# ext_sensor_board.net
KiCad netlist of a schematic drawn in EAGLE
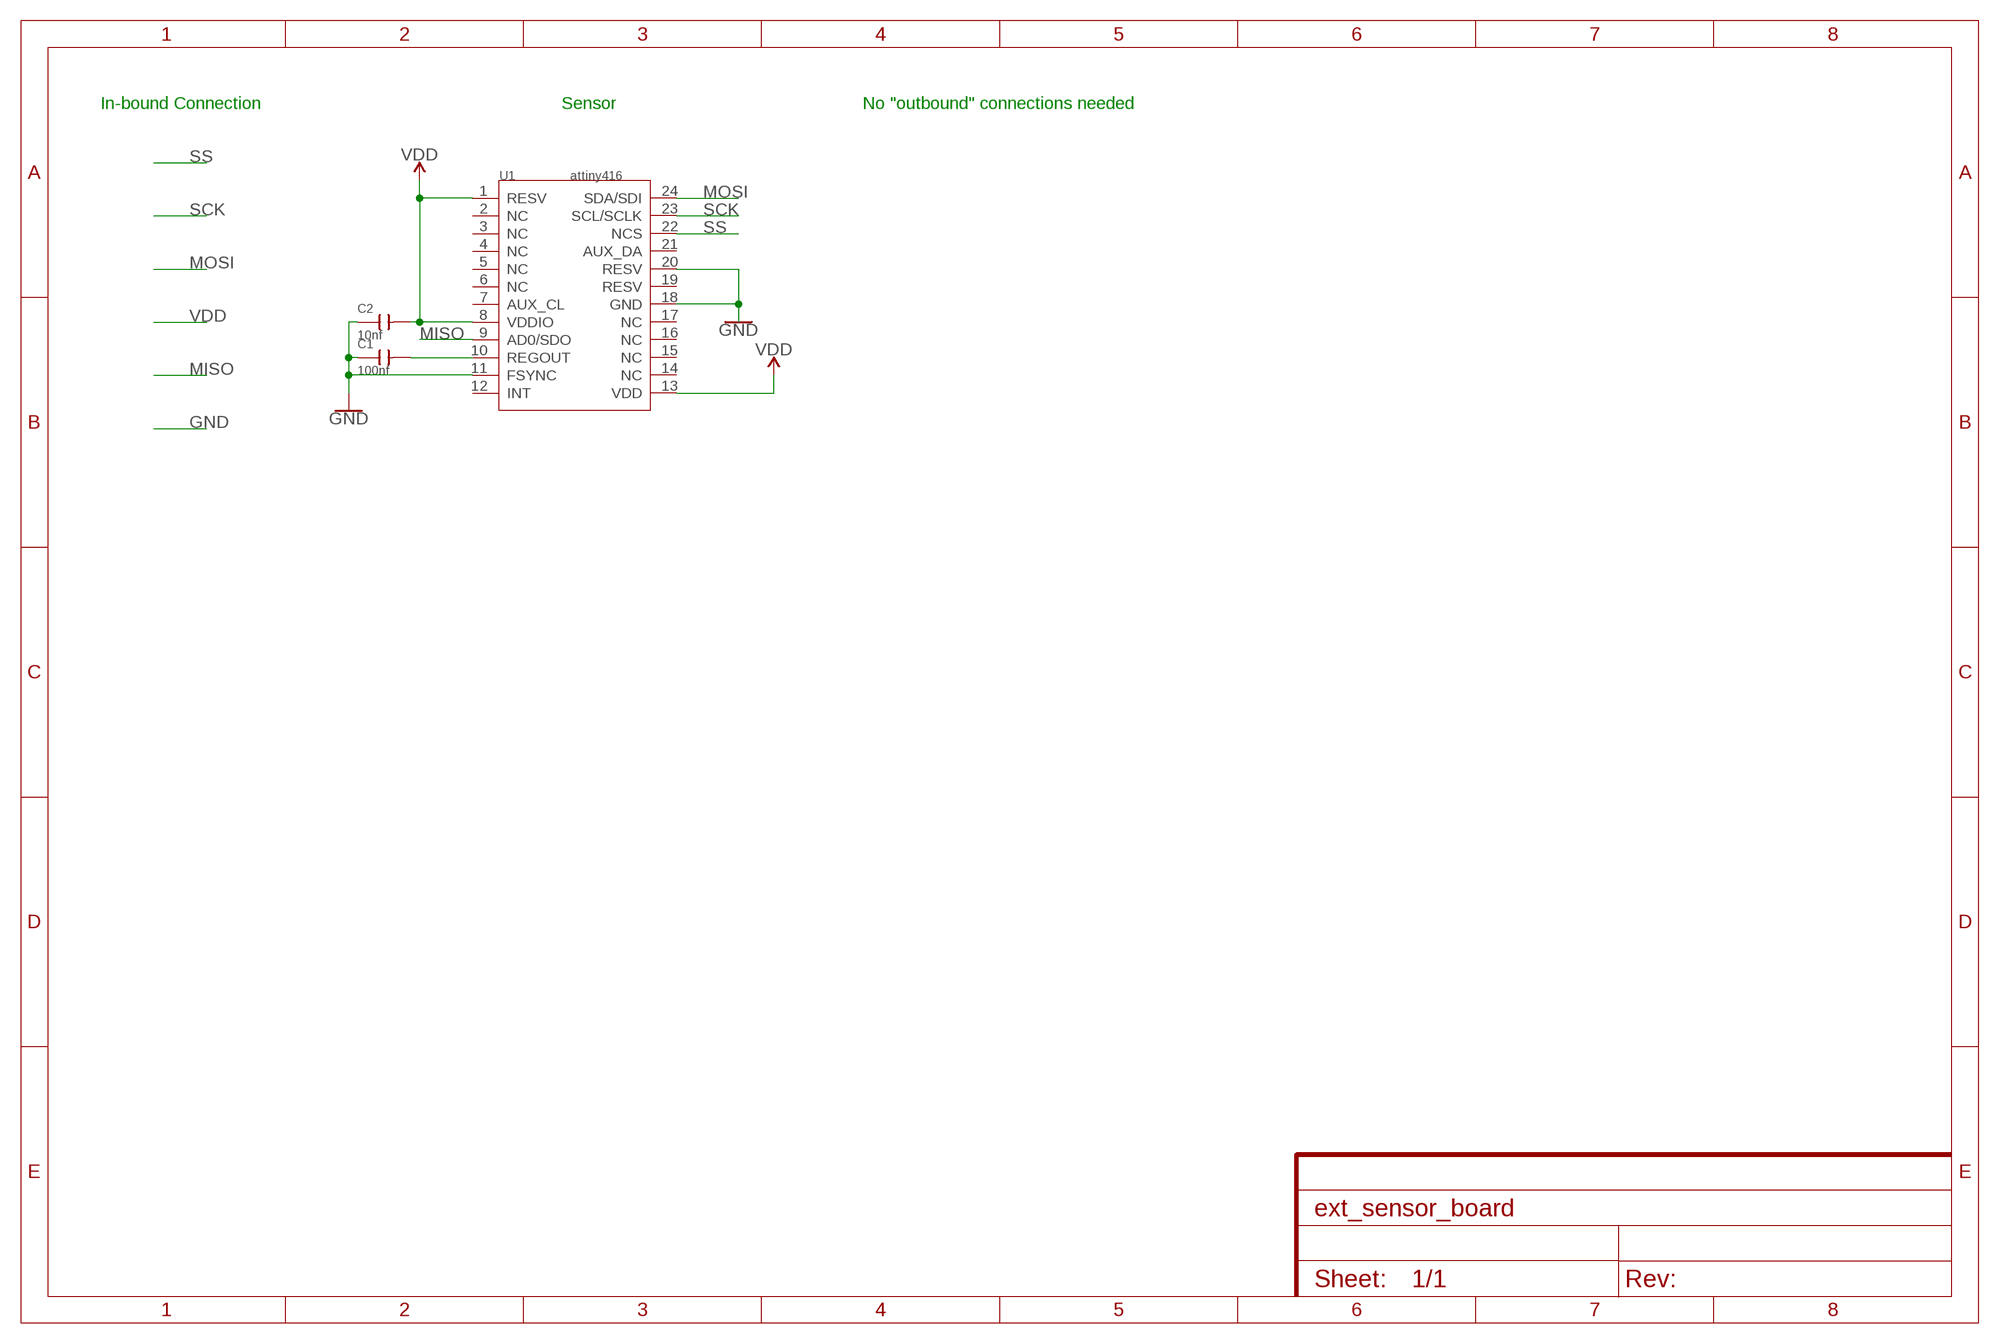
[diagram p0: schematic, sheet 1]

(export (version "E")
  (design (tool "Eeschema 10.0.6"))
  (components
    (comp (ref "C1")
      (value "100nf")
      (footprint "eagle-import:C0402")
      (fields (field (name "MPN") "CC0402KRX7R8BB104"))
      (libsource (lib "eagle-import") (part "CERAMIC-100NF-25V-10%-X7R(0402)"))
    )
    (comp (ref "C2")
      (value "10nf")
      (footprint "eagle-import:C0402")
      (fields (field (name "MPN") "CC0402KRX7R9BB103"))
      (libsource (lib "eagle-import") (part "CERAMIC-10NF-50V-10%-X7R(0402)"))
    )
    (comp (ref "U1")
      (value "attiny416")
      (footprint "eagle-import:QFN24G-0.4-3X3MM")
      (libsource (lib "eagle-import") (part "MOTION/POSITION-MPU-9250(QFN24G)"))
    )
  )
  (nets
    (net (code "1") (name "/MISO") (class "Default")
      (node (ref "U1") (pin "9") (pinfunction "AD0/SDO_9") (pintype "bidirectional"))
    )
    (net (code "2") (name "/MOSI") (class "Default")
      (node (ref "U1") (pin "24") (pinfunction "SDA/SDI_24") (pintype "bidirectional"))
    )
    (net (code "3") (name "/SCK") (class "Default")
      (node (ref "U1") (pin "23") (pinfunction "SCL/SCLK_23") (pintype "bidirectional"))
    )
    (net (code "4") (name "/SS") (class "Default")
      (node (ref "U1") (pin "22") (pinfunction "NCS_22") (pintype "bidirectional"))
    )
    (net (code "5") (name "GND") (class "Default")
      (node (ref "C1") (pin "1") (pinfunction "1_1") (pintype "passive"))
      (node (ref "C2") (pin "1") (pinfunction "1_1") (pintype "passive"))
      (node (ref "U1") (pin "11") (pinfunction "FSYNC_11") (pintype "bidirectional"))
      (node (ref "U1") (pin "18") (pinfunction "GND_18") (pintype "bidirectional"))
      (node (ref "U1") (pin "20") (pinfunction "RESV_20") (pintype "bidirectional"))
    )
    (net (code "6") (name "Net-(U1-REGOUT)") (class "Default")
      (node (ref "C1") (pin "2") (pinfunction "2_2") (pintype "passive"))
      (node (ref "U1") (pin "10") (pinfunction "REGOUT_10") (pintype "bidirectional"))
    )
    (net (code "7") (name "VDD") (class "Default")
      (node (ref "C2") (pin "2") (pinfunction "2_2") (pintype "passive"))
      (node (ref "U1") (pin "1") (pinfunction "RESV_1") (pintype "bidirectional"))
      (node (ref "U1") (pin "13") (pinfunction "VDD_13") (pintype "bidirectional"))
      (node (ref "U1") (pin "8") (pinfunction "VDDIO_8") (pintype "bidirectional"))
    )
    (net (code "8") (name "unconnected-(U1-AUX_CL-Pad7)") (class "Default")
      (node (ref "U1") (pin "7") (pinfunction "AUX_CL_7") (pintype "bidirectional"))
    )
    (net (code "9") (name "unconnected-(U1-AUX_DA-Pad21)") (class "Default")
      (node (ref "U1") (pin "21") (pinfunction "AUX_DA_21") (pintype "bidirectional"))
    )
    (net (code "10") (name "unconnected-(U1-INT-Pad12)") (class "Default")
      (node (ref "U1") (pin "12") (pinfunction "INT_12") (pintype "bidirectional"))
    )
    (net (code "11") (name "unconnected-(U1-NC-Pad2)") (class "Default")
      (node (ref "U1") (pin "2") (pinfunction "NC_2") (pintype "bidirectional"))
    )
    (net (code "12") (name "unconnected-(U1-NC-Pad3)") (class "Default")
      (node (ref "U1") (pin "3") (pinfunction "NC_3") (pintype "bidirectional"))
    )
    (net (code "13") (name "unconnected-(U1-NC-Pad4)") (class "Default")
      (node (ref "U1") (pin "4") (pinfunction "NC_4") (pintype "bidirectional"))
    )
    (net (code "14") (name "unconnected-(U1-NC-Pad5)") (class "Default")
      (node (ref "U1") (pin "5") (pinfunction "NC_5") (pintype "bidirectional"))
    )
    (net (code "15") (name "unconnected-(U1-NC-Pad6)") (class "Default")
      (node (ref "U1") (pin "6") (pinfunction "NC_6") (pintype "bidirectional"))
    )
    (net (code "16") (name "unconnected-(U1-NC-Pad14)") (class "Default")
      (node (ref "U1") (pin "14") (pinfunction "NC_14") (pintype "bidirectional"))
    )
    (net (code "17") (name "unconnected-(U1-NC-Pad15)") (class "Default")
      (node (ref "U1") (pin "15") (pinfunction "NC_15") (pintype "bidirectional"))
    )
    (net (code "18") (name "unconnected-(U1-NC-Pad16)") (class "Default")
      (node (ref "U1") (pin "16") (pinfunction "NC_16") (pintype "bidirectional"))
    )
    (net (code "19") (name "unconnected-(U1-NC-Pad17)") (class "Default")
      (node (ref "U1") (pin "17") (pinfunction "NC_17") (pintype "bidirectional"))
    )
    (net (code "20") (name "unconnected-(U1-RESV-Pad19)") (class "Default")
      (node (ref "U1") (pin "19") (pinfunction "RESV_19") (pintype "bidirectional"))
    )
  )
)
